# Sheet3.net
KiCad netlist of a schematic drawn in Altium Designer
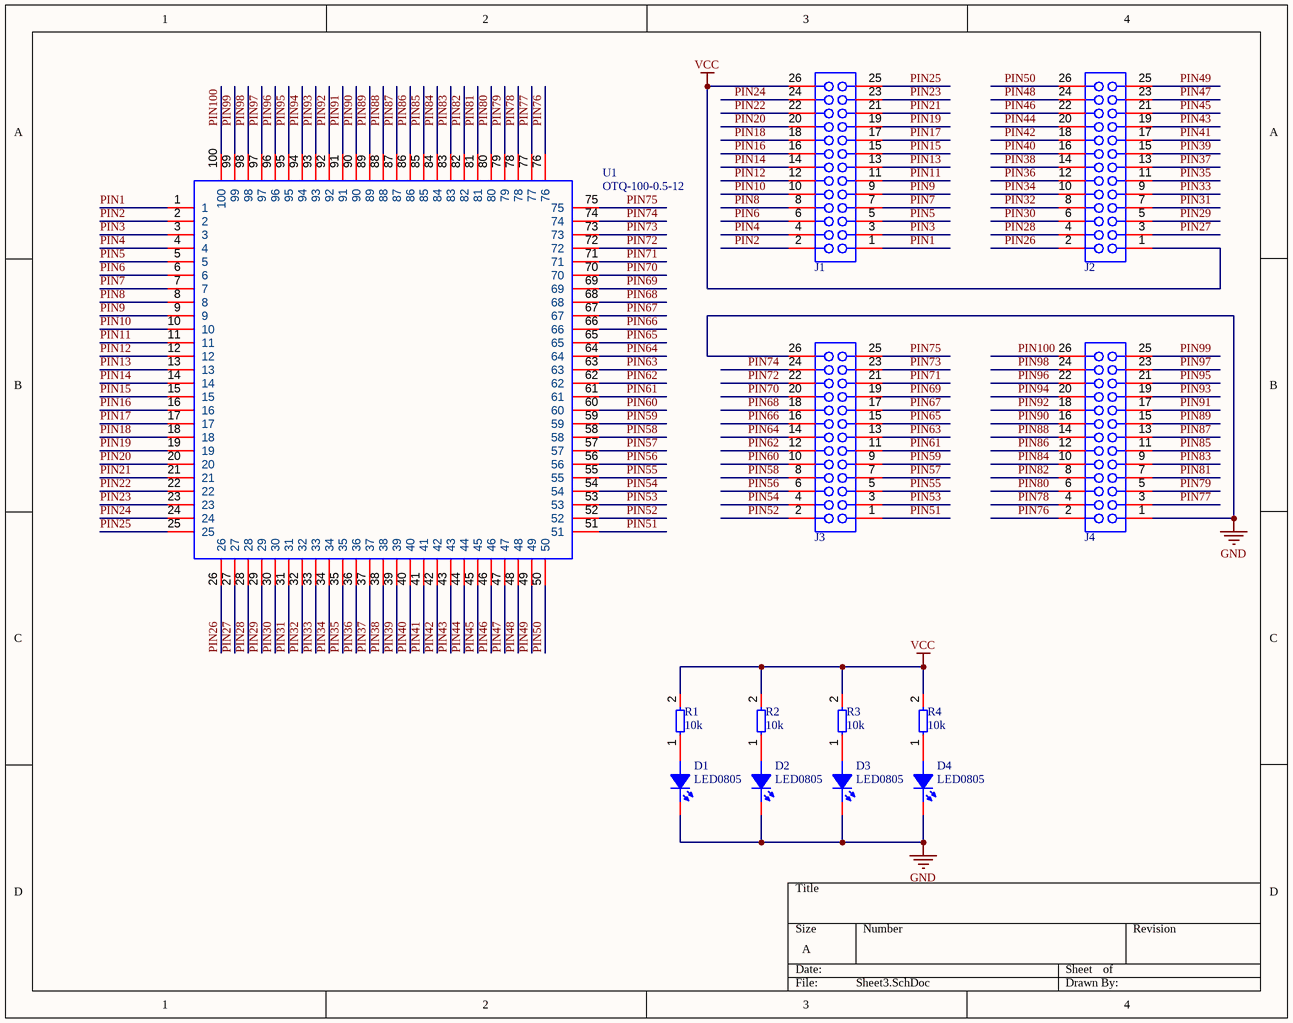
[diagram p0: Sheet3.SchDoc]

(export (version "E")
  (design (tool "Eeschema 10.0.6"))
  (components
    (comp (ref "D1") (value "LED0805") (footprint "L0805RED") (libsource (lib "SMDLibrary") (part "LED0805")))
    (comp (ref "D2") (value "LED0805") (footprint "L0805RED") (libsource (lib "SMDLibrary") (part "LED0805")))
    (comp (ref "D3") (value "LED0805") (footprint "L0805RED") (libsource (lib "SMDLibrary") (part "LED0805")))
    (comp (ref "D4") (value "LED0805") (footprint "L0805RED") (libsource (lib "SMDLibrary") (part "LED0805")))
    (comp (ref "J1")
      (value "Header 13x2 TH Pitch 2.54mm")
      (footprint "Header 13x2 TH Pitch 2.54mm")
      (libsource (lib "SMDLibrary") (part "Header 13x2 TH Pitch 2.54mm"))
    )
    (comp (ref "J2")
      (value "Header 13x2 TH Pitch 2.54mm")
      (footprint "Header 13x2 TH Pitch 2.54mm")
      (libsource (lib "SMDLibrary") (part "Header 13x2 TH Pitch 2.54mm"))
    )
    (comp (ref "J3")
      (value "Header 13x2 TH Pitch 2.54mm")
      (footprint "Header 13x2 TH Pitch 2.54mm")
      (libsource (lib "SMDLibrary") (part "Header 13x2 TH Pitch 2.54mm"))
    )
    (comp (ref "J4")
      (value "Header 13x2 TH Pitch 2.54mm")
      (footprint "Header 13x2 TH Pitch 2.54mm")
      (libsource (lib "SMDLibrary") (part "Header 13x2 TH Pitch 2.54mm"))
    )
    (comp (ref "R1") (value "10k") (footprint "R0805") (libsource (lib "SMDLibrary") (part "Resistor SMD")))
    (comp (ref "R2") (value "10k") (footprint "R0805") (libsource (lib "SMDLibrary") (part "Resistor SMD")))
    (comp (ref "R3") (value "10k") (footprint "R0805") (libsource (lib "SMDLibrary") (part "Resistor SMD")))
    (comp (ref "R4") (value "10k") (footprint "R0805") (libsource (lib "SMDLibrary") (part "Resistor SMD")))
    (comp (ref "U1")
      (value "OTQ-100-0.5-12")
      (footprint "SOCKET_ENPLAS_OTQ-100-0.5-12")
      (libsource (lib "SMDLibrary") (part "SOCKET_ENPLAS_OTQ-100-0.5-12"))
    )
  )
  (nets
    (net (code "1") (name "/PIN1") (class "Default")
      (node (ref "J1") (pin "1") (pinfunction "1_1") (pintype "passive"))
      (node (ref "U1") (pin "1") (pinfunction "1_1") (pintype "passive"))
    )
    (net (code "2") (name "/PIN2") (class "Default")
      (node (ref "J1") (pin "2") (pinfunction "2_2") (pintype "passive"))
      (node (ref "U1") (pin "2") (pinfunction "2_2") (pintype "passive"))
    )
    (net (code "3") (name "/PIN3") (class "Default")
      (node (ref "J1") (pin "3") (pinfunction "3_3") (pintype "passive"))
      (node (ref "U1") (pin "3") (pinfunction "3_3") (pintype "passive"))
    )
    (net (code "4") (name "/PIN4") (class "Default")
      (node (ref "J1") (pin "4") (pinfunction "4_4") (pintype "passive"))
      (node (ref "U1") (pin "4") (pinfunction "4_4") (pintype "passive"))
    )
    (net (code "5") (name "/PIN5") (class "Default")
      (node (ref "J1") (pin "5") (pinfunction "5_5") (pintype "passive"))
      (node (ref "U1") (pin "5") (pinfunction "5_5") (pintype "passive"))
    )
    (net (code "6") (name "/PIN6") (class "Default")
      (node (ref "J1") (pin "6") (pinfunction "6_6") (pintype "passive"))
      (node (ref "U1") (pin "6") (pinfunction "6_6") (pintype "passive"))
    )
    (net (code "7") (name "/PIN7") (class "Default")
      (node (ref "J1") (pin "7") (pinfunction "7_7") (pintype "passive"))
      (node (ref "U1") (pin "7") (pinfunction "7_7") (pintype "passive"))
    )
    (net (code "8") (name "/PIN8") (class "Default")
      (node (ref "J1") (pin "8") (pinfunction "8_8") (pintype "passive"))
      (node (ref "U1") (pin "8") (pinfunction "8_8") (pintype "passive"))
    )
    (net (code "9") (name "/PIN9") (class "Default")
      (node (ref "J1") (pin "9") (pinfunction "9_9") (pintype "passive"))
      (node (ref "U1") (pin "9") (pinfunction "9_9") (pintype "passive"))
    )
    (net (code "10") (name "/PIN10") (class "Default")
      (node (ref "J1") (pin "10") (pinfunction "10_10") (pintype "passive"))
      (node (ref "U1") (pin "10") (pinfunction "10_10") (pintype "passive"))
    )
    (net (code "11") (name "/PIN11") (class "Default")
      (node (ref "J1") (pin "11") (pinfunction "11_11") (pintype "passive"))
      (node (ref "U1") (pin "11") (pinfunction "11_11") (pintype "passive"))
    )
    (net (code "12") (name "/PIN12") (class "Default")
      (node (ref "J1") (pin "12") (pinfunction "12_12") (pintype "passive"))
      (node (ref "U1") (pin "12") (pinfunction "12_12") (pintype "passive"))
    )
    (net (code "13") (name "/PIN13") (class "Default")
      (node (ref "J1") (pin "13") (pinfunction "13_13") (pintype "passive"))
      (node (ref "U1") (pin "13") (pinfunction "13_13") (pintype "passive"))
    )
    (net (code "14") (name "/PIN14") (class "Default")
      (node (ref "J1") (pin "14") (pinfunction "14_14") (pintype "passive"))
      (node (ref "U1") (pin "14") (pinfunction "14_14") (pintype "passive"))
    )
    (net (code "15") (name "/PIN15") (class "Default")
      (node (ref "J1") (pin "15") (pinfunction "15_15") (pintype "passive"))
      (node (ref "U1") (pin "15") (pinfunction "15_15") (pintype "passive"))
    )
    (net (code "16") (name "/PIN16") (class "Default")
      (node (ref "J1") (pin "16") (pinfunction "16_16") (pintype "passive"))
      (node (ref "U1") (pin "16") (pinfunction "16_16") (pintype "passive"))
    )
    (net (code "17") (name "/PIN17") (class "Default")
      (node (ref "J1") (pin "17") (pinfunction "17_17") (pintype "passive"))
      (node (ref "U1") (pin "17") (pinfunction "17_17") (pintype "passive"))
    )
    (net (code "18") (name "/PIN18") (class "Default")
      (node (ref "J1") (pin "18") (pinfunction "18_18") (pintype "passive"))
      (node (ref "U1") (pin "18") (pinfunction "18_18") (pintype "passive"))
    )
    (net (code "19") (name "/PIN19") (class "Default")
      (node (ref "J1") (pin "19") (pinfunction "19_19") (pintype "passive"))
      (node (ref "U1") (pin "19") (pinfunction "19_19") (pintype "passive"))
    )
    (net (code "20") (name "/PIN20") (class "Default")
      (node (ref "J1") (pin "20") (pinfunction "20_20") (pintype "passive"))
      (node (ref "U1") (pin "20") (pinfunction "20_20") (pintype "passive"))
    )
    (net (code "21") (name "/PIN21") (class "Default")
      (node (ref "J1") (pin "21") (pinfunction "21_21") (pintype "passive"))
      (node (ref "U1") (pin "21") (pinfunction "21_21") (pintype "passive"))
    )
    (net (code "22") (name "/PIN22") (class "Default")
      (node (ref "J1") (pin "22") (pinfunction "22_22") (pintype "passive"))
      (node (ref "U1") (pin "22") (pinfunction "22_22") (pintype "passive"))
    )
    (net (code "23") (name "/PIN23") (class "Default")
      (node (ref "J1") (pin "23") (pinfunction "23_23") (pintype "passive"))
      (node (ref "U1") (pin "23") (pinfunction "23_23") (pintype "passive"))
    )
    (net (code "24") (name "/PIN24") (class "Default")
      (node (ref "J1") (pin "24") (pinfunction "24_24") (pintype "passive"))
      (node (ref "U1") (pin "24") (pinfunction "24_24") (pintype "passive"))
    )
    (net (code "25") (name "/PIN25") (class "Default")
      (node (ref "J1") (pin "25") (pinfunction "25_25") (pintype "passive"))
      (node (ref "U1") (pin "25") (pinfunction "25_25") (pintype "passive"))
    )
    (net (code "26") (name "/PIN26") (class "Default")
      (node (ref "J2") (pin "2") (pinfunction "2_2") (pintype "passive"))
      (node (ref "U1") (pin "26") (pinfunction "26_26") (pintype "passive"))
    )
    (net (code "27") (name "/PIN27") (class "Default")
      (node (ref "J2") (pin "3") (pinfunction "3_3") (pintype "passive"))
      (node (ref "U1") (pin "27") (pinfunction "27_27") (pintype "passive"))
    )
    (net (code "28") (name "/PIN28") (class "Default")
      (node (ref "J2") (pin "4") (pinfunction "4_4") (pintype "passive"))
      (node (ref "U1") (pin "28") (pinfunction "28_28") (pintype "passive"))
    )
    (net (code "29") (name "/PIN29") (class "Default")
      (node (ref "J2") (pin "5") (pinfunction "5_5") (pintype "passive"))
      (node (ref "U1") (pin "29") (pinfunction "29_29") (pintype "passive"))
    )
    (net (code "30") (name "/PIN30") (class "Default")
      (node (ref "J2") (pin "6") (pinfunction "6_6") (pintype "passive"))
      (node (ref "U1") (pin "30") (pinfunction "30_30") (pintype "passive"))
    )
    (net (code "31") (name "/PIN31") (class "Default")
      (node (ref "J2") (pin "7") (pinfunction "7_7") (pintype "passive"))
      (node (ref "U1") (pin "31") (pinfunction "31_31") (pintype "passive"))
    )
    (net (code "32") (name "/PIN32") (class "Default")
      (node (ref "J2") (pin "8") (pinfunction "8_8") (pintype "passive"))
      (node (ref "U1") (pin "32") (pinfunction "32_32") (pintype "passive"))
    )
    (net (code "33") (name "/PIN33") (class "Default")
      (node (ref "J2") (pin "9") (pinfunction "9_9") (pintype "passive"))
      (node (ref "U1") (pin "33") (pinfunction "33_33") (pintype "passive"))
    )
    (net (code "34") (name "/PIN34") (class "Default")
      (node (ref "J2") (pin "10") (pinfunction "10_10") (pintype "passive"))
      (node (ref "U1") (pin "34") (pinfunction "34_34") (pintype "passive"))
    )
    (net (code "35") (name "/PIN35") (class "Default")
      (node (ref "J2") (pin "11") (pinfunction "11_11") (pintype "passive"))
      (node (ref "U1") (pin "35") (pinfunction "35_35") (pintype "passive"))
    )
    (net (code "36") (name "/PIN36") (class "Default")
      (node (ref "J2") (pin "12") (pinfunction "12_12") (pintype "passive"))
      (node (ref "U1") (pin "36") (pinfunction "36_36") (pintype "passive"))
    )
    (net (code "37") (name "/PIN37") (class "Default")
      (node (ref "J2") (pin "13") (pinfunction "13_13") (pintype "passive"))
      (node (ref "U1") (pin "37") (pinfunction "37_37") (pintype "passive"))
    )
    (net (code "38") (name "/PIN38") (class "Default")
      (node (ref "J2") (pin "14") (pinfunction "14_14") (pintype "passive"))
      (node (ref "U1") (pin "38") (pinfunction "38_38") (pintype "passive"))
    )
    (net (code "39") (name "/PIN39") (class "Default")
      (node (ref "J2") (pin "15") (pinfunction "15_15") (pintype "passive"))
      (node (ref "U1") (pin "39") (pinfunction "39_39") (pintype "passive"))
    )
    (net (code "40") (name "/PIN40") (class "Default")
      (node (ref "J2") (pin "16") (pinfunction "16_16") (pintype "passive"))
      (node (ref "U1") (pin "40") (pinfunction "40_40") (pintype "passive"))
    )
    (net (code "41") (name "/PIN41") (class "Default")
      (node (ref "J2") (pin "17") (pinfunction "17_17") (pintype "passive"))
      (node (ref "U1") (pin "41") (pinfunction "41_41") (pintype "passive"))
    )
    (net (code "42") (name "/PIN42") (class "Default")
      (node (ref "J2") (pin "18") (pinfunction "18_18") (pintype "passive"))
      (node (ref "U1") (pin "42") (pinfunction "42_42") (pintype "passive"))
    )
    (net (code "43") (name "/PIN43") (class "Default")
      (node (ref "J2") (pin "19") (pinfunction "19_19") (pintype "passive"))
      (node (ref "U1") (pin "43") (pinfunction "43_43") (pintype "passive"))
    )
    (net (code "44") (name "/PIN44") (class "Default")
      (node (ref "J2") (pin "20") (pinfunction "20_20") (pintype "passive"))
      (node (ref "U1") (pin "44") (pinfunction "44_44") (pintype "passive"))
    )
    (net (code "45") (name "/PIN45") (class "Default")
      (node (ref "J2") (pin "21") (pinfunction "21_21") (pintype "passive"))
      (node (ref "U1") (pin "45") (pinfunction "45_45") (pintype "passive"))
    )
    (net (code "46") (name "/PIN46") (class "Default")
      (node (ref "J2") (pin "22") (pinfunction "22_22") (pintype "passive"))
      (node (ref "U1") (pin "46") (pinfunction "46_46") (pintype "passive"))
    )
    (net (code "47") (name "/PIN47") (class "Default")
      (node (ref "J2") (pin "23") (pinfunction "23_23") (pintype "passive"))
      (node (ref "U1") (pin "47") (pinfunction "47_47") (pintype "passive"))
    )
    (net (code "48") (name "/PIN48") (class "Default")
      (node (ref "J2") (pin "24") (pinfunction "24_24") (pintype "passive"))
      (node (ref "U1") (pin "48") (pinfunction "48_48") (pintype "passive"))
    )
    (net (code "49") (name "/PIN49") (class "Default")
      (node (ref "J2") (pin "25") (pinfunction "25_25") (pintype "passive"))
      (node (ref "U1") (pin "49") (pinfunction "49_49") (pintype "passive"))
    )
    (net (code "50") (name "/PIN50") (class "Default")
      (node (ref "J2") (pin "26") (pinfunction "26_26") (pintype "passive"))
      (node (ref "U1") (pin "50") (pinfunction "50_50") (pintype "passive"))
    )
    (net (code "51") (name "/PIN51") (class "Default")
      (node (ref "J3") (pin "1") (pinfunction "1_1") (pintype "passive"))
      (node (ref "U1") (pin "51") (pinfunction "51_51") (pintype "passive"))
    )
    (net (code "52") (name "/PIN52") (class "Default")
      (node (ref "J3") (pin "2") (pinfunction "2_2") (pintype "passive"))
      (node (ref "U1") (pin "52") (pinfunction "52_52") (pintype "passive"))
    )
    (net (code "53") (name "/PIN53") (class "Default")
      (node (ref "J3") (pin "3") (pinfunction "3_3") (pintype "passive"))
      (node (ref "U1") (pin "53") (pinfunction "53_53") (pintype "passive"))
    )
    (net (code "54") (name "/PIN54") (class "Default")
      (node (ref "J3") (pin "4") (pinfunction "4_4") (pintype "passive"))
      (node (ref "U1") (pin "54") (pinfunction "54_54") (pintype "passive"))
    )
    (net (code "55") (name "/PIN55") (class "Default")
      (node (ref "J3") (pin "5") (pinfunction "5_5") (pintype "passive"))
      (node (ref "U1") (pin "55") (pinfunction "55_55") (pintype "passive"))
    )
    (net (code "56") (name "/PIN56") (class "Default")
      (node (ref "J3") (pin "6") (pinfunction "6_6") (pintype "passive"))
      (node (ref "U1") (pin "56") (pinfunction "56_56") (pintype "passive"))
    )
    (net (code "57") (name "/PIN57") (class "Default")
      (node (ref "J3") (pin "7") (pinfunction "7_7") (pintype "passive"))
      (node (ref "U1") (pin "57") (pinfunction "57_57") (pintype "passive"))
    )
    (net (code "58") (name "/PIN58") (class "Default")
      (node (ref "J3") (pin "8") (pinfunction "8_8") (pintype "passive"))
      (node (ref "U1") (pin "58") (pinfunction "58_58") (pintype "passive"))
    )
    (net (code "59") (name "/PIN59") (class "Default")
      (node (ref "J3") (pin "9") (pinfunction "9_9") (pintype "passive"))
      (node (ref "U1") (pin "59") (pinfunction "59_59") (pintype "passive"))
    )
    (net (code "60") (name "/PIN60") (class "Default")
      (node (ref "J3") (pin "10") (pinfunction "10_10") (pintype "passive"))
      (node (ref "U1") (pin "60") (pinfunction "60_60") (pintype "passive"))
    )
    (net (code "61") (name "/PIN61") (class "Default")
      (node (ref "J3") (pin "11") (pinfunction "11_11") (pintype "passive"))
      (node (ref "U1") (pin "61") (pinfunction "61_61") (pintype "passive"))
    )
    (net (code "62") (name "/PIN62") (class "Default")
      (node (ref "J3") (pin "12") (pinfunction "12_12") (pintype "passive"))
      (node (ref "U1") (pin "62") (pinfunction "62_62") (pintype "passive"))
    )
    (net (code "63") (name "/PIN63") (class "Default")
      (node (ref "J3") (pin "13") (pinfunction "13_13") (pintype "passive"))
      (node (ref "U1") (pin "63") (pinfunction "63_63") (pintype "passive"))
    )
    (net (code "64") (name "/PIN64") (class "Default")
      (node (ref "J3") (pin "14") (pinfunction "14_14") (pintype "passive"))
      (node (ref "U1") (pin "64") (pinfunction "64_64") (pintype "passive"))
    )
    (net (code "65") (name "/PIN65") (class "Default")
      (node (ref "J3") (pin "15") (pinfunction "15_15") (pintype "passive"))
      (node (ref "U1") (pin "65") (pinfunction "65_65") (pintype "passive"))
    )
    (net (code "66") (name "/PIN66") (class "Default")
      (node (ref "J3") (pin "16") (pinfunction "16_16") (pintype "passive"))
      (node (ref "U1") (pin "66") (pinfunction "66_66") (pintype "passive"))
    )
    (net (code "67") (name "/PIN67") (class "Default")
      (node (ref "J3") (pin "17") (pinfunction "17_17") (pintype "passive"))
      (node (ref "U1") (pin "67") (pinfunction "67_67") (pintype "passive"))
    )
    (net (code "68") (name "/PIN68") (class "Default")
      (node (ref "J3") (pin "18") (pinfunction "18_18") (pintype "passive"))
      (node (ref "U1") (pin "68") (pinfunction "68_68") (pintype "passive"))
    )
    (net (code "69") (name "/PIN69") (class "Default")
      (node (ref "J3") (pin "19") (pinfunction "19_19") (pintype "passive"))
      (node (ref "U1") (pin "69") (pinfunction "69_69") (pintype "passive"))
    )
    (net (code "70") (name "/PIN70") (class "Default")
      (node (ref "J3") (pin "20") (pinfunction "20_20") (pintype "passive"))
      (node (ref "U1") (pin "70") (pinfunction "70_70") (pintype "passive"))
    )
    (net (code "71") (name "/PIN71") (class "Default")
      (node (ref "J3") (pin "21") (pinfunction "21_21") (pintype "passive"))
      (node (ref "U1") (pin "71") (pinfunction "71_71") (pintype "passive"))
    )
    (net (code "72") (name "/PIN72") (class "Default")
      (node (ref "J3") (pin "22") (pinfunction "22_22") (pintype "passive"))
      (node (ref "U1") (pin "72") (pinfunction "72_72") (pintype "passive"))
    )
    (net (code "73") (name "/PIN73") (class "Default")
      (node (ref "J3") (pin "23") (pinfunction "23_23") (pintype "passive"))
      (node (ref "U1") (pin "73") (pinfunction "73_73") (pintype "passive"))
    )
    (net (code "74") (name "/PIN74") (class "Default")
      (node (ref "J3") (pin "24") (pinfunction "24_24") (pintype "passive"))
      (node (ref "U1") (pin "74") (pinfunction "74_74") (pintype "passive"))
    )
    (net (code "75") (name "/PIN75") (class "Default")
      (node (ref "J3") (pin "25") (pinfunction "25_25") (pintype "passive"))
      (node (ref "U1") (pin "75") (pinfunction "75_75") (pintype "passive"))
    )
    (net (code "76") (name "/PIN76") (class "Default")
      (node (ref "J4") (pin "2") (pinfunction "2_2") (pintype "passive"))
      (node (ref "U1") (pin "76") (pinfunction "76_76") (pintype "passive"))
    )
    (net (code "77") (name "/PIN77") (class "Default")
      (node (ref "J4") (pin "3") (pinfunction "3_3") (pintype "passive"))
      (node (ref "U1") (pin "77") (pinfunction "77_77") (pintype "passive"))
    )
    (net (code "78") (name "/PIN78") (class "Default")
      (node (ref "J4") (pin "4") (pinfunction "4_4") (pintype "passive"))
      (node (ref "U1") (pin "78") (pinfunction "78_78") (pintype "passive"))
    )
    (net (code "79") (name "/PIN79") (class "Default")
      (node (ref "J4") (pin "5") (pinfunction "5_5") (pintype "passive"))
      (node (ref "U1") (pin "79") (pinfunction "79_79") (pintype "passive"))
    )
    (net (code "80") (name "/PIN80") (class "Default")
      (node (ref "J4") (pin "6") (pinfunction "6_6") (pintype "passive"))
      (node (ref "U1") (pin "80") (pinfunction "80_80") (pintype "passive"))
    )
    (net (code "81") (name "/PIN81") (class "Default")
      (node (ref "J4") (pin "7") (pinfunction "7_7") (pintype "passive"))
      (node (ref "U1") (pin "81") (pinfunction "81_81") (pintype "passive"))
    )
    (net (code "82") (name "/PIN82") (class "Default")
      (node (ref "J4") (pin "8") (pinfunction "8_8") (pintype "passive"))
      (node (ref "U1") (pin "82") (pinfunction "82_82") (pintype "passive"))
    )
    (net (code "83") (name "/PIN83") (class "Default")
      (node (ref "J4") (pin "9") (pinfunction "9_9") (pintype "passive"))
      (node (ref "U1") (pin "83") (pinfunction "83_83") (pintype "passive"))
    )
    (net (code "84") (name "/PIN84") (class "Default")
      (node (ref "J4") (pin "10") (pinfunction "10_10") (pintype "passive"))
      (node (ref "U1") (pin "84") (pinfunction "84_84") (pintype "passive"))
    )
    (net (code "85") (name "/PIN85") (class "Default")
      (node (ref "J4") (pin "11") (pinfunction "11_11") (pintype "passive"))
      (node (ref "U1") (pin "85") (pinfunction "85_85") (pintype "passive"))
    )
    (net (code "86") (name "/PIN86") (class "Default")
      (node (ref "J4") (pin "12") (pinfunction "12_12") (pintype "passive"))
      (node (ref "U1") (pin "86") (pinfunction "86_86") (pintype "passive"))
    )
    (net (code "87") (name "/PIN87") (class "Default")
      (node (ref "J4") (pin "13") (pinfunction "13_13") (pintype "passive"))
      (node (ref "U1") (pin "87") (pinfunction "87_87") (pintype "passive"))
    )
    (net (code "88") (name "/PIN88") (class "Default")
      (node (ref "J4") (pin "14") (pinfunction "14_14") (pintype "passive"))
      (node (ref "U1") (pin "88") (pinfunction "88_88") (pintype "passive"))
    )
    (net (code "89") (name "/PIN89") (class "Default")
      (node (ref "J4") (pin "15") (pinfunction "15_15") (pintype "passive"))
      (node (ref "U1") (pin "89") (pinfunction "89_89") (pintype "passive"))
    )
    (net (code "90") (name "/PIN90") (class "Default")
      (node (ref "J4") (pin "16") (pinfunction "16_16") (pintype "passive"))
      (node (ref "U1") (pin "90") (pinfunction "90_90") (pintype "passive"))
    )
    (net (code "91") (name "/PIN91") (class "Default")
      (node (ref "J4") (pin "17") (pinfunction "17_17") (pintype "passive"))
      (node (ref "U1") (pin "91") (pinfunction "91_91") (pintype "passive"))
    )
    (net (code "92") (name "/PIN92") (class "Default")
      (node (ref "J4") (pin "18") (pinfunction "18_18") (pintype "passive"))
      (node (ref "U1") (pin "92") (pinfunction "92_92") (pintype "passive"))
    )
    (net (code "93") (name "/PIN93") (class "Default")
      (node (ref "J4") (pin "19") (pinfunction "19_19") (pintype "passive"))
      (node (ref "U1") (pin "93") (pinfunction "93_93") (pintype "passive"))
    )
    (net (code "94") (name "/PIN94") (class "Default")
      (node (ref "J4") (pin "20") (pinfunction "20_20") (pintype "passive"))
      (node (ref "U1") (pin "94") (pinfunction "94_94") (pintype "passive"))
    )
    (net (code "95") (name "/PIN95") (class "Default")
      (node (ref "J4") (pin "21") (pinfunction "21_21") (pintype "passive"))
      (node (ref "U1") (pin "95") (pinfunction "95_95") (pintype "passive"))
    )
    (net (code "96") (name "/PIN96") (class "Default")
      (node (ref "J4") (pin "22") (pinfunction "22_22") (pintype "passive"))
      (node (ref "U1") (pin "96") (pinfunction "96_96") (pintype "passive"))
    )
    (net (code "97") (name "/PIN97") (class "Default")
      (node (ref "J4") (pin "23") (pinfunction "23_23") (pintype "passive"))
      (node (ref "U1") (pin "97") (pinfunction "97_97") (pintype "passive"))
    )
    (net (code "98") (name "/PIN98") (class "Default")
      (node (ref "J4") (pin "24") (pinfunction "24_24") (pintype "passive"))
      (node (ref "U1") (pin "98") (pinfunction "98_98") (pintype "passive"))
    )
    (net (code "99") (name "/PIN99") (class "Default")
      (node (ref "J4") (pin "25") (pinfunction "25_25") (pintype "passive"))
      (node (ref "U1") (pin "99") (pinfunction "99_99") (pintype "passive"))
    )
    (net (code "100") (name "/PIN100") (class "Default")
      (node (ref "J4") (pin "26") (pinfunction "26_26") (pintype "passive"))
      (node (ref "U1") (pin "100") (pinfunction "100_100") (pintype "passive"))
    )
    (net (code "101") (name "GND") (class "Default")
      (node (ref "D1") (pin "2") (pinfunction "K_2") (pintype "passive"))
      (node (ref "D2") (pin "2") (pinfunction "K_2") (pintype "passive"))
      (node (ref "D3") (pin "2") (pinfunction "K_2") (pintype "passive"))
      (node (ref "D4") (pin "2") (pinfunction "K_2") (pintype "passive"))
      (node (ref "J3") (pin "26") (pinfunction "26_26") (pintype "passive"))
      (node (ref "J4") (pin "1") (pinfunction "1_1") (pintype "passive"))
    )
    (net (code "102") (name "Net-(D1-A)") (class "Default")
      (node (ref "D1") (pin "1") (pinfunction "A_1") (pintype "passive"))
      (node (ref "R1") (pin "1") (pinfunction "1_1") (pintype "passive"))
    )
    (net (code "103") (name "Net-(D2-A)") (class "Default")
      (node (ref "D2") (pin "1") (pinfunction "A_1") (pintype "passive"))
      (node (ref "R2") (pin "1") (pinfunction "1_1") (pintype "passive"))
    )
    (net (code "104") (name "Net-(D3-A)") (class "Default")
      (node (ref "D3") (pin "1") (pinfunction "A_1") (pintype "passive"))
      (node (ref "R3") (pin "1") (pinfunction "1_1") (pintype "passive"))
    )
    (net (code "105") (name "Net-(D4-A)") (class "Default")
      (node (ref "D4") (pin "1") (pinfunction "A_1") (pintype "passive"))
      (node (ref "R4") (pin "1") (pinfunction "1_1") (pintype "passive"))
    )
    (net (code "106") (name "VCC") (class "Default")
      (node (ref "J1") (pin "26") (pinfunction "26_26") (pintype "passive"))
      (node (ref "J2") (pin "1") (pinfunction "1_1") (pintype "passive"))
      (node (ref "R1") (pin "2") (pinfunction "2_2") (pintype "passive"))
      (node (ref "R2") (pin "2") (pinfunction "2_2") (pintype "passive"))
      (node (ref "R3") (pin "2") (pinfunction "2_2") (pintype "passive"))
      (node (ref "R4") (pin "2") (pinfunction "2_2") (pintype "passive"))
    )
  )
)
